# pH_Orp_Board.net
KiCad netlist of a schematic drawn in Altium Designer
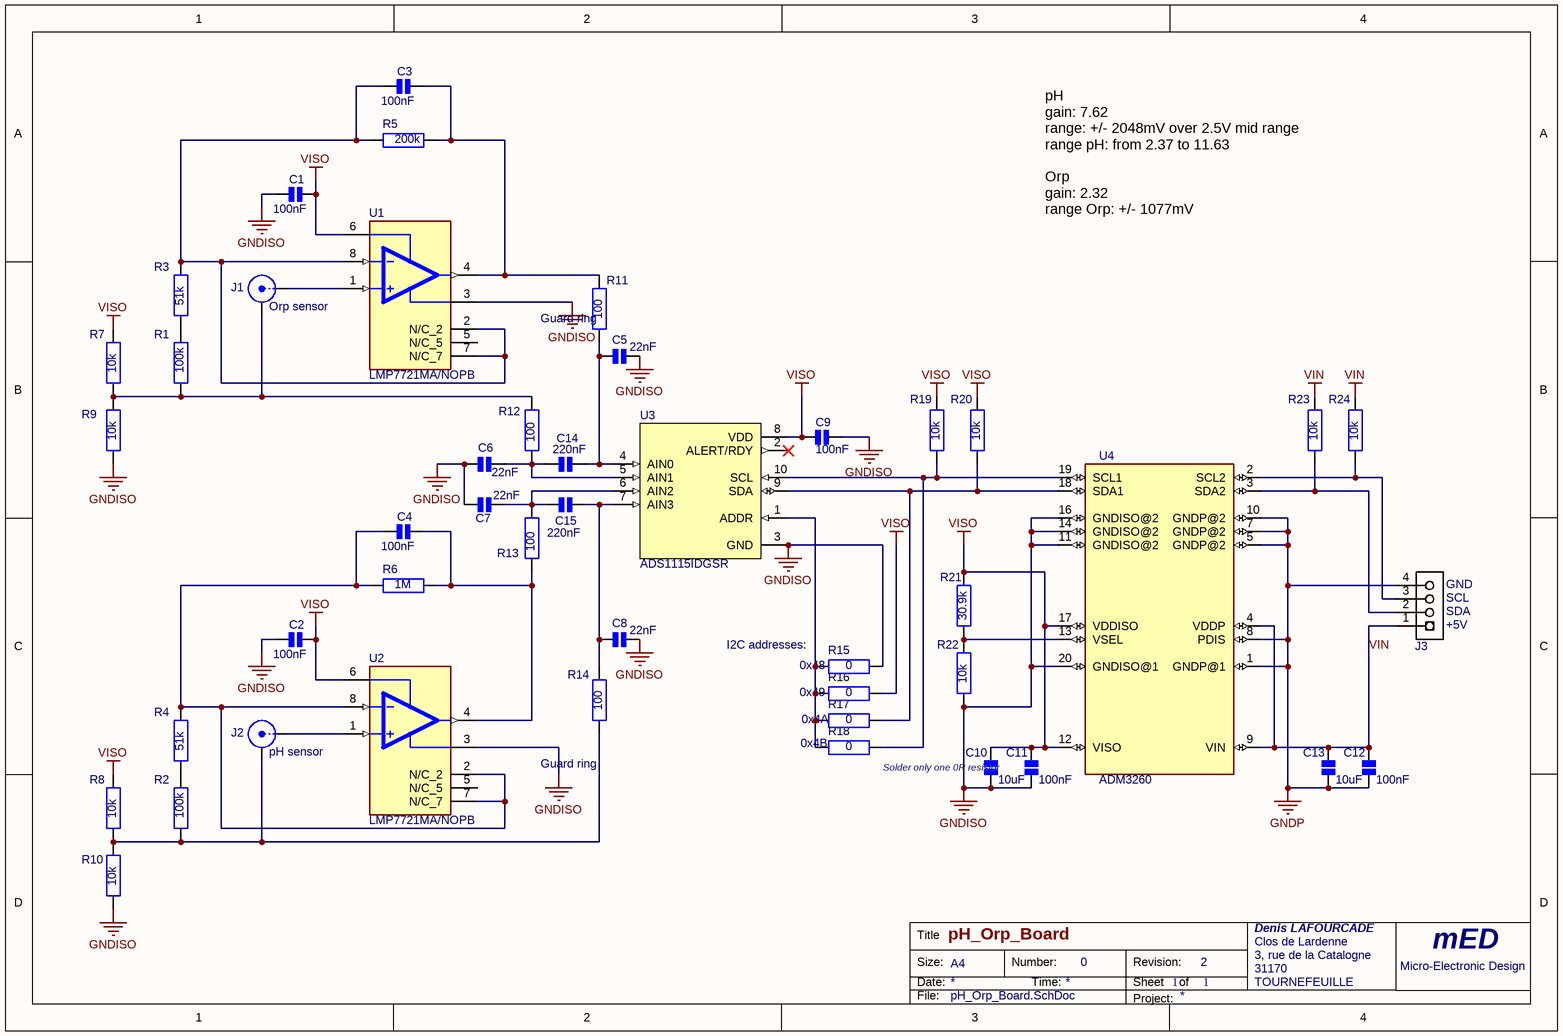
[diagram p0: pH_Orp_Board.SchDoc]

(export (version "E")
  (design (tool "Eeschema 10.0.6"))
  (components
    (comp (ref "C1")
      (value "100nF")
      (footprint "vh_altium_library:0805C-GENERIC")
      (description "Capacitor")
      (libsource (lib "Miscellaneous Devices") (part "CAP"))
    )
    (comp (ref "C2")
      (value "100nF")
      (footprint "vh_altium_library:0805C-GENERIC")
      (description "Capacitor")
      (libsource (lib "Miscellaneous Devices") (part "CAP"))
    )
    (comp (ref "C3")
      (value "100nF")
      (footprint "vh_altium_library:0805C-GENERIC")
      (description "Capacitor")
      (libsource (lib "Miscellaneous Devices") (part "CAP"))
    )
    (comp (ref "C4")
      (value "100nF")
      (footprint "vh_altium_library:0805C-GENERIC")
      (description "Capacitor")
      (libsource (lib "Miscellaneous Devices") (part "CAP"))
    )
    (comp (ref "C5")
      (value "22nF")
      (footprint "vh_altium_library:0805C-GENERIC")
      (description "Capacitor")
      (libsource (lib "Miscellaneous Devices") (part "CAP"))
    )
    (comp (ref "C6")
      (value "22nF")
      (footprint "vh_altium_library:0805C-GENERIC")
      (description "Capacitor")
      (libsource (lib "Miscellaneous Devices") (part "CAP"))
    )
    (comp (ref "C7")
      (value "22nF")
      (footprint "vh_altium_library:0805C-GENERIC")
      (description "Capacitor")
      (libsource (lib "Miscellaneous Devices") (part "CAP"))
    )
    (comp (ref "C8")
      (value "22nF")
      (footprint "vh_altium_library:0805C-GENERIC")
      (description "Capacitor")
      (libsource (lib "Miscellaneous Devices") (part "CAP"))
    )
    (comp (ref "C9")
      (value "100nF")
      (footprint "vh_altium_library:0805C-GENERIC")
      (description "Capacitor")
      (libsource (lib "Miscellaneous Devices") (part "CAP"))
    )
    (comp (ref "C10")
      (value "10uF")
      (footprint "vh_altium_library:0805C-GENERIC")
      (description "Capacitor")
      (libsource (lib "") (part "CAP_1"))
    )
    (comp (ref "C11")
      (value "100nF")
      (footprint "vh_altium_library:0805C-GENERIC")
      (description "Capacitor")
      (libsource (lib "") (part "CAP_1"))
    )
    (comp (ref "C12")
      (value "100nF")
      (footprint "vh_altium_library:0805C-GENERIC")
      (description "Capacitor")
      (libsource (lib "") (part "CAP_1"))
    )
    (comp (ref "C13")
      (value "10uF")
      (footprint "vh_altium_library:0805C-GENERIC")
      (description "Capacitor")
      (libsource (lib "") (part "CAP_1"))
    )
    (comp (ref "C14")
      (value "220nF")
      (footprint "vh_altium_library:0805C-GENERIC")
      (description "Capacitor")
      (libsource (lib "Miscellaneous Devices") (part "CAP"))
    )
    (comp (ref "C15")
      (value "220nF")
      (footprint "vh_altium_library:0805C-GENERIC")
      (description "Capacitor")
      (libsource (lib "Miscellaneous Devices") (part "CAP"))
    )
    (comp (ref "J1")
      (value "Orp sensor")
      (footprint "BNC_RA CON")
      (description "BNC Elbow Connector")
      (fields (field (name "PUBLISHER") "Altium Limited"))
      (libsource (lib "Miscellaneous Connectors") (part "BNC"))
    )
    (comp (ref "J2")
      (value "pH sensor")
      (footprint "BNC_RA CON")
      (description "BNC Elbow Connector")
      (fields (field (name "PUBLISHER") "Altium Limited"))
      (libsource (lib "Miscellaneous Connectors") (part "BNC"))
    )
    (comp (ref "J3")
      (value "HEADER-1X4")
      (footprint "HEADER-1X4")
      (libsource (lib "vh_altium_library") (part "HEADER-1X4"))
    )
    (comp (ref "R1")
      (value "100k")
      (footprint "0805R-100K")
      (description "Resistor")
      (libsource (lib "Miscellaneous Devices") (part "RES2"))
    )
    (comp (ref "R2")
      (value "100k")
      (footprint "0805R-100K")
      (description "Resistor")
      (libsource (lib "Miscellaneous Devices") (part "RES2"))
    )
    (comp (ref "R3")
      (value "51k")
      (footprint "0805R-56K")
      (description "Resistor")
      (libsource (lib "Miscellaneous Devices") (part "RES2"))
    )
    (comp (ref "R4")
      (value "51k")
      (footprint "0805R-56K")
      (description "Resistor")
      (libsource (lib "Miscellaneous Devices") (part "RES2"))
    )
    (comp (ref "R5")
      (value "200k")
      (footprint "0805R-220K")
      (description "Resistor")
      (libsource (lib "Miscellaneous Devices") (part "RES2"))
    )
    (comp (ref "R6")
      (value "1M")
      (footprint "0805R-TBD")
      (description "Resistor")
      (libsource (lib "Miscellaneous Devices") (part "RES2"))
    )
    (comp (ref "R7")
      (value "10k")
      (footprint "0805R-10K")
      (description "Resistor")
      (libsource (lib "Miscellaneous Devices") (part "RES2"))
    )
    (comp (ref "R8")
      (value "10k")
      (footprint "0805R-10K")
      (description "Resistor")
      (libsource (lib "Miscellaneous Devices") (part "RES2"))
    )
    (comp (ref "R9")
      (value "10k")
      (footprint "0805R-10K")
      (description "Resistor")
      (libsource (lib "Miscellaneous Devices") (part "RES2"))
    )
    (comp (ref "R10")
      (value "10k")
      (footprint "0805R-10K")
      (description "Resistor")
      (libsource (lib "Miscellaneous Devices") (part "RES2"))
    )
    (comp (ref "R11")
      (value "100")
      (footprint "0805R-100")
      (description "Resistor")
      (libsource (lib "Miscellaneous Devices") (part "RES2"))
    )
    (comp (ref "R12")
      (value "100")
      (footprint "0805R-100")
      (description "Resistor")
      (libsource (lib "Miscellaneous Devices") (part "RES2"))
    )
    (comp (ref "R13")
      (value "100")
      (footprint "0805R-100")
      (description "Resistor")
      (libsource (lib "Miscellaneous Devices") (part "RES2"))
    )
    (comp (ref "R14")
      (value "100")
      (footprint "0805R-100")
      (description "Resistor")
      (libsource (lib "Miscellaneous Devices") (part "RES2"))
    )
    (comp (ref "R15")
      (value "0")
      (footprint "0805R-0R1")
      (description "Resistor")
      (libsource (lib "Miscellaneous Devices") (part "RES2"))
    )
    (comp (ref "R16")
      (value "0")
      (footprint "0805R-0R1")
      (description "Resistor")
      (libsource (lib "Miscellaneous Devices") (part "RES2"))
    )
    (comp (ref "R17")
      (value "0")
      (footprint "0805R-0R1")
      (description "Resistor")
      (libsource (lib "Miscellaneous Devices") (part "RES2"))
    )
    (comp (ref "R18")
      (value "0")
      (footprint "0805R-0R1")
      (description "Resistor")
      (libsource (lib "Miscellaneous Devices") (part "RES2"))
    )
    (comp (ref "R19")
      (value "10k")
      (footprint "vh_altium_library:0805R-10K")
      (description "Resistor")
      (libsource (lib "Miscellaneous Devices") (part "RES2"))
    )
    (comp (ref "R20")
      (value "10k")
      (footprint "0805R-10K")
      (description "Resistor")
      (libsource (lib "Miscellaneous Devices") (part "RES2"))
    )
    (comp (ref "R21")
      (value "30.9k")
      (footprint "0805R-33K")
      (description "Resistor")
      (libsource (lib "Miscellaneous Devices") (part "RES2"))
    )
    (comp (ref "R22")
      (value "10k")
      (footprint "0805R-10K")
      (description "Resistor")
      (libsource (lib "Miscellaneous Devices") (part "RES2"))
    )
    (comp (ref "R23")
      (value "10k")
      (footprint "vh_altium_library:0805R-10K")
      (description "Resistor")
      (libsource (lib "Miscellaneous Devices") (part "RES2"))
    )
    (comp (ref "R24")
      (value "10k")
      (footprint "0805R-10K")
      (description "Resistor")
      (libsource (lib "Miscellaneous Devices") (part "RES2"))
    )
    (comp (ref "U1")
      (value "LMP7721MA/NOPB")
      (footprint "SOIC127P599X175-8N")
      (description "3 Femtoampere Input Bias Current Precision Amplifier 8-SOIC -40 to 125")
      (fields (field (name "MF") "Texas Instruments"))
      (libsource (lib "LMP7721MA_NOPB") (part "LMP7721MA/NOPB"))
    )
    (comp (ref "U2")
      (value "LMP7721MA/NOPB")
      (footprint "SOIC127P599X175-8N")
      (description "3 Femtoampere Input Bias Current Precision Amplifier 8-SOIC -40 to 125")
      (fields (field (name "MF") "Texas Instruments"))
      (libsource (lib "LMP7721MA_NOPB") (part "LMP7721MA/NOPB"))
    )
    (comp (ref "U3")
      (value "ADS1115IDGSR")
      (footprint "SOP50P490X110-10N")
      (fields (field (name "MP") "altium_native_batch"))
      (libsource (lib "ADS1115IDGSR") (part "ADS1115IDGSR"))
    )
    (comp (ref "U4")
      (value "ADM3260")
      (footprint "SOP65P780X200-20N")
      (description "IÂ²C Digital Isolator 2500Vrms 2 Channel - 25kV/Âµs CMTI 20-SSOP (0.209, 5.30mm Width)")
      (fields (field (name "MF") "Analog Devices"))
      (libsource (lib "ADM3260") (part "ADM3260"))
    )
  )
  (nets
    (net (code "1") (name "GNDISO") (class "Default")
      (node (ref "C1") (pin "1") (pinfunction "1_1") (pintype "passive"))
      (node (ref "C10") (pin "2") (pinfunction "2_2") (pintype "passive"))
      (node (ref "C11") (pin "2") (pinfunction "2_2") (pintype "passive"))
      (node (ref "C2") (pin "1") (pinfunction "1_1") (pintype "passive"))
      (node (ref "C5") (pin "2") (pinfunction "2_2") (pintype "passive"))
      (node (ref "C6") (pin "1") (pinfunction "1_1") (pintype "passive"))
      (node (ref "C7") (pin "1") (pinfunction "1_1") (pintype "passive"))
      (node (ref "C8") (pin "2") (pinfunction "2_2") (pintype "passive"))
      (node (ref "C9") (pin "2") (pinfunction "2_2") (pintype "passive"))
      (node (ref "R10") (pin "1") (pinfunction "1_1") (pintype "passive"))
      (node (ref "R15") (pin "2") (pinfunction "2_2") (pintype "passive"))
      (node (ref "R22") (pin "1") (pinfunction "1_1") (pintype "passive"))
      (node (ref "R9") (pin "1") (pinfunction "1_1") (pintype "passive"))
      (node (ref "U1") (pin "3") (pinfunction "V-_3") (pintype "power_in"))
      (node (ref "U2") (pin "3") (pinfunction "V-_3") (pintype "power_in"))
      (node (ref "U3") (pin "3") (pinfunction "GND_3") (pintype "power_in"))
      (node (ref "U4") (pin "11") (pinfunction "GNDISO@2_11") (pintype "bidirectional"))
      (node (ref "U4") (pin "14") (pinfunction "GNDISO@2_14") (pintype "bidirectional"))
      (node (ref "U4") (pin "16") (pinfunction "GNDISO@2_16") (pintype "bidirectional"))
      (node (ref "U4") (pin "20") (pinfunction "GNDISO@1_20") (pintype "bidirectional"))
    )
    (net (code "2") (name "GNDP") (class "Default")
      (node (ref "C12") (pin "2") (pinfunction "2_2") (pintype "passive"))
      (node (ref "C13") (pin "2") (pinfunction "2_2") (pintype "passive"))
      (node (ref "J3") (pin "4") (pintype "passive"))
      (node (ref "U4") (pin "1") (pinfunction "GNDP@1_1") (pintype "bidirectional"))
      (node (ref "U4") (pin "10") (pinfunction "GNDP@2_10") (pintype "bidirectional"))
      (node (ref "U4") (pin "5") (pinfunction "GNDP@2_5") (pintype "bidirectional"))
      (node (ref "U4") (pin "7") (pinfunction "GNDP@2_7") (pintype "bidirectional"))
      (node (ref "U4") (pin "8") (pinfunction "PDIS_8") (pintype "bidirectional"))
    )
    (net (code "3") (name "Net-(J1-X)") (class "Default")
      (node (ref "J1") (pin "1") (pinfunction "X_1") (pintype "passive"))
      (node (ref "U1") (pin "1") (pinfunction "IN+_1") (pintype "input"))
    )
    (net (code "4") (name "Net-(J1-Y)") (class "Default")
      (node (ref "J1") (pin "2") (pinfunction "Y_2") (pintype "passive"))
      (node (ref "R1") (pin "1") (pinfunction "1_1") (pintype "passive"))
      (node (ref "R12") (pin "1") (pinfunction "1_1") (pintype "passive"))
      (node (ref "R7") (pin "1") (pinfunction "1_1") (pintype "passive"))
      (node (ref "R9") (pin "2") (pinfunction "2_2") (pintype "passive"))
    )
    (net (code "5") (name "Net-(J2-X)") (class "Default")
      (node (ref "J2") (pin "1") (pinfunction "X_1") (pintype "passive"))
      (node (ref "U2") (pin "1") (pinfunction "IN+_1") (pintype "input"))
    )
    (net (code "6") (name "Net-(J2-Y)") (class "Default")
      (node (ref "J2") (pin "2") (pinfunction "Y_2") (pintype "passive"))
      (node (ref "R10") (pin "2") (pinfunction "2_2") (pintype "passive"))
      (node (ref "R14") (pin "1") (pinfunction "1_1") (pintype "passive"))
      (node (ref "R2") (pin "1") (pinfunction "1_1") (pintype "passive"))
      (node (ref "R8") (pin "1") (pinfunction "1_1") (pintype "passive"))
    )
    (net (code "7") (name "Net-(R1-Pad2)") (class "Default")
      (node (ref "R1") (pin "2") (pinfunction "2_2") (pintype "passive"))
      (node (ref "R3") (pin "1") (pinfunction "1_1") (pintype "passive"))
    )
    (net (code "8") (name "Net-(R2-Pad2)") (class "Default")
      (node (ref "R2") (pin "2") (pinfunction "2_2") (pintype "passive"))
      (node (ref "R4") (pin "1") (pinfunction "1_1") (pintype "passive"))
    )
    (net (code "9") (name "Net-(U1-IN-)") (class "Default")
      (node (ref "C3") (pin "1") (pinfunction "1_1") (pintype "passive"))
      (node (ref "R3") (pin "2") (pinfunction "2_2") (pintype "passive"))
      (node (ref "R5") (pin "2") (pinfunction "2_2") (pintype "passive"))
      (node (ref "U1") (pin "2") (pinfunction "N/C_2_2") (pintype "passive"))
      (node (ref "U1") (pin "7") (pinfunction "N/C_7_7") (pintype "passive"))
      (node (ref "U1") (pin "8") (pinfunction "IN-_8") (pintype "input"))
    )
    (net (code "10") (name "Net-(U1-VOUT)") (class "Default")
      (node (ref "C3") (pin "2") (pinfunction "2_2") (pintype "passive"))
      (node (ref "R11") (pin "2") (pinfunction "2_2") (pintype "passive"))
      (node (ref "R5") (pin "1") (pinfunction "1_1") (pintype "passive"))
      (node (ref "U1") (pin "4") (pinfunction "VOUT_4") (pintype "output"))
    )
    (net (code "11") (name "Net-(U2-IN-)") (class "Default")
      (node (ref "C4") (pin "1") (pinfunction "1_1") (pintype "passive"))
      (node (ref "R4") (pin "2") (pinfunction "2_2") (pintype "passive"))
      (node (ref "R6") (pin "2") (pinfunction "2_2") (pintype "passive"))
      (node (ref "U2") (pin "2") (pinfunction "N/C_2_2") (pintype "passive"))
      (node (ref "U2") (pin "7") (pinfunction "N/C_7_7") (pintype "passive"))
      (node (ref "U2") (pin "8") (pinfunction "IN-_8") (pintype "input"))
    )
    (net (code "12") (name "Net-(U2-VOUT)") (class "Default")
      (node (ref "C4") (pin "2") (pinfunction "2_2") (pintype "passive"))
      (node (ref "R13") (pin "2") (pinfunction "2_2") (pintype "passive"))
      (node (ref "R6") (pin "1") (pinfunction "1_1") (pintype "passive"))
      (node (ref "U2") (pin "4") (pinfunction "VOUT_4") (pintype "output"))
    )
    (net (code "13") (name "Net-(U3-ADDR)") (class "Default")
      (node (ref "R15") (pin "1") (pinfunction "1_1") (pintype "passive"))
      (node (ref "R16") (pin "1") (pinfunction "1_1") (pintype "passive"))
      (node (ref "R17") (pin "1") (pinfunction "1_1") (pintype "passive"))
      (node (ref "R18") (pin "1") (pinfunction "1_1") (pintype "passive"))
      (node (ref "U3") (pin "1") (pinfunction "ADDR_1") (pintype "input"))
    )
    (net (code "14") (name "Net-(U3-AIN0)") (class "Default")
      (node (ref "C14") (pin "2") (pinfunction "2_2") (pintype "passive"))
      (node (ref "C5") (pin "1") (pinfunction "1_1") (pintype "passive"))
      (node (ref "R11") (pin "1") (pinfunction "1_1") (pintype "passive"))
      (node (ref "U3") (pin "4") (pinfunction "AIN0_4") (pintype "input"))
    )
    (net (code "15") (name "Net-(U3-AIN1)") (class "Default")
      (node (ref "C14") (pin "1") (pinfunction "1_1") (pintype "passive"))
      (node (ref "C6") (pin "2") (pinfunction "2_2") (pintype "passive"))
      (node (ref "R12") (pin "2") (pinfunction "2_2") (pintype "passive"))
      (node (ref "U3") (pin "5") (pinfunction "AIN1_5") (pintype "input"))
    )
    (net (code "16") (name "Net-(U3-AIN2)") (class "Default")
      (node (ref "C15") (pin "1") (pinfunction "1_1") (pintype "passive"))
      (node (ref "C7") (pin "2") (pinfunction "2_2") (pintype "passive"))
      (node (ref "R13") (pin "1") (pinfunction "1_1") (pintype "passive"))
      (node (ref "U3") (pin "6") (pinfunction "AIN2_6") (pintype "input"))
    )
    (net (code "17") (name "Net-(U3-AIN3)") (class "Default")
      (node (ref "C15") (pin "2") (pinfunction "2_2") (pintype "passive"))
      (node (ref "C8") (pin "1") (pinfunction "1_1") (pintype "passive"))
      (node (ref "R14") (pin "2") (pinfunction "2_2") (pintype "passive"))
      (node (ref "U3") (pin "7") (pinfunction "AIN3_7") (pintype "input"))
    )
    (net (code "18") (name "Net-(U3-SCL)") (class "Default")
      (node (ref "R18") (pin "2") (pinfunction "2_2") (pintype "passive"))
      (node (ref "R19") (pin "1") (pinfunction "1_1") (pintype "passive"))
      (node (ref "U3") (pin "10") (pinfunction "SCL_10") (pintype "input"))
      (node (ref "U4") (pin "19") (pinfunction "SCL1_19") (pintype "bidirectional"))
    )
    (net (code "19") (name "Net-(U3-SDA)") (class "Default")
      (node (ref "R17") (pin "2") (pinfunction "2_2") (pintype "passive"))
      (node (ref "R20") (pin "1") (pinfunction "1_1") (pintype "passive"))
      (node (ref "U3") (pin "9") (pinfunction "SDA_9") (pintype "bidirectional"))
      (node (ref "U4") (pin "18") (pinfunction "SDA1_18") (pintype "bidirectional"))
    )
    (net (code "20") (name "Net-(U4-SCL2)") (class "Default")
      (node (ref "J3") (pin "3") (pintype "passive"))
      (node (ref "R24") (pin "1") (pinfunction "1_1") (pintype "passive"))
      (node (ref "U4") (pin "2") (pinfunction "SCL2_2") (pintype "bidirectional"))
    )
    (net (code "21") (name "Net-(U4-SDA2)") (class "Default")
      (node (ref "J3") (pin "2") (pintype "passive"))
      (node (ref "R23") (pin "1") (pinfunction "1_1") (pintype "passive"))
      (node (ref "U4") (pin "3") (pinfunction "SDA2_3") (pintype "bidirectional"))
    )
    (net (code "22") (name "Net-(U4-VSEL)") (class "Default")
      (node (ref "R21") (pin "1") (pinfunction "1_1") (pintype "passive"))
      (node (ref "R22") (pin "2") (pinfunction "2_2") (pintype "passive"))
      (node (ref "U4") (pin "13") (pinfunction "VSEL_13") (pintype "bidirectional"))
    )
    (net (code "23") (name "VIN") (class "Default")
      (node (ref "C12") (pin "1") (pinfunction "1_1") (pintype "passive"))
      (node (ref "C13") (pin "1") (pinfunction "1_1") (pintype "passive"))
      (node (ref "J3") (pin "1") (pintype "passive"))
      (node (ref "R23") (pin "2") (pinfunction "2_2") (pintype "passive"))
      (node (ref "R24") (pin "2") (pinfunction "2_2") (pintype "passive"))
      (node (ref "U4") (pin "4") (pinfunction "VDDP_4") (pintype "bidirectional"))
      (node (ref "U4") (pin "9") (pinfunction "VIN_9") (pintype "bidirectional"))
    )
    (net (code "24") (name "VISO") (class "Default")
      (node (ref "C1") (pin "2") (pinfunction "2_2") (pintype "passive"))
      (node (ref "C10") (pin "1") (pinfunction "1_1") (pintype "passive"))
      (node (ref "C11") (pin "1") (pinfunction "1_1") (pintype "passive"))
      (node (ref "C2") (pin "2") (pinfunction "2_2") (pintype "passive"))
      (node (ref "C9") (pin "1") (pinfunction "1_1") (pintype "passive"))
      (node (ref "R16") (pin "2") (pinfunction "2_2") (pintype "passive"))
      (node (ref "R19") (pin "2") (pinfunction "2_2") (pintype "passive"))
      (node (ref "R20") (pin "2") (pinfunction "2_2") (pintype "passive"))
      (node (ref "R21") (pin "2") (pinfunction "2_2") (pintype "passive"))
      (node (ref "R7") (pin "2") (pinfunction "2_2") (pintype "passive"))
      (node (ref "R8") (pin "2") (pinfunction "2_2") (pintype "passive"))
      (node (ref "U1") (pin "6") (pinfunction "V+_6") (pintype "power_in"))
      (node (ref "U2") (pin "6") (pinfunction "V+_6") (pintype "power_in"))
      (node (ref "U3") (pin "8") (pinfunction "VDD_8") (pintype "power_in"))
      (node (ref "U4") (pin "12") (pinfunction "VISO_12") (pintype "bidirectional"))
      (node (ref "U4") (pin "17") (pinfunction "VDDISO_17") (pintype "bidirectional"))
    )
    (net (code "25") (name "unconnected-(U1-N{slash}C_5-Pad5)") (class "Default")
      (node (ref "U1") (pin "5") (pinfunction "N/C_5_5") (pintype "passive"))
    )
    (net (code "26") (name "unconnected-(U2-N{slash}C_5-Pad5)") (class "Default")
      (node (ref "U2") (pin "5") (pinfunction "N/C_5_5") (pintype "passive"))
    )
    (net (code "27") (name "unconnected-(U3-ALERT{slash}RDY-Pad2)") (class "Default")
      (node (ref "U3") (pin "2") (pinfunction "ALERT/RDY_2") (pintype "output+no_connect"))
    )
  )
)
